# SCH_10_1HD_2022-05-30.net
KiCad netlist of a schematic drawn in EasyEDA
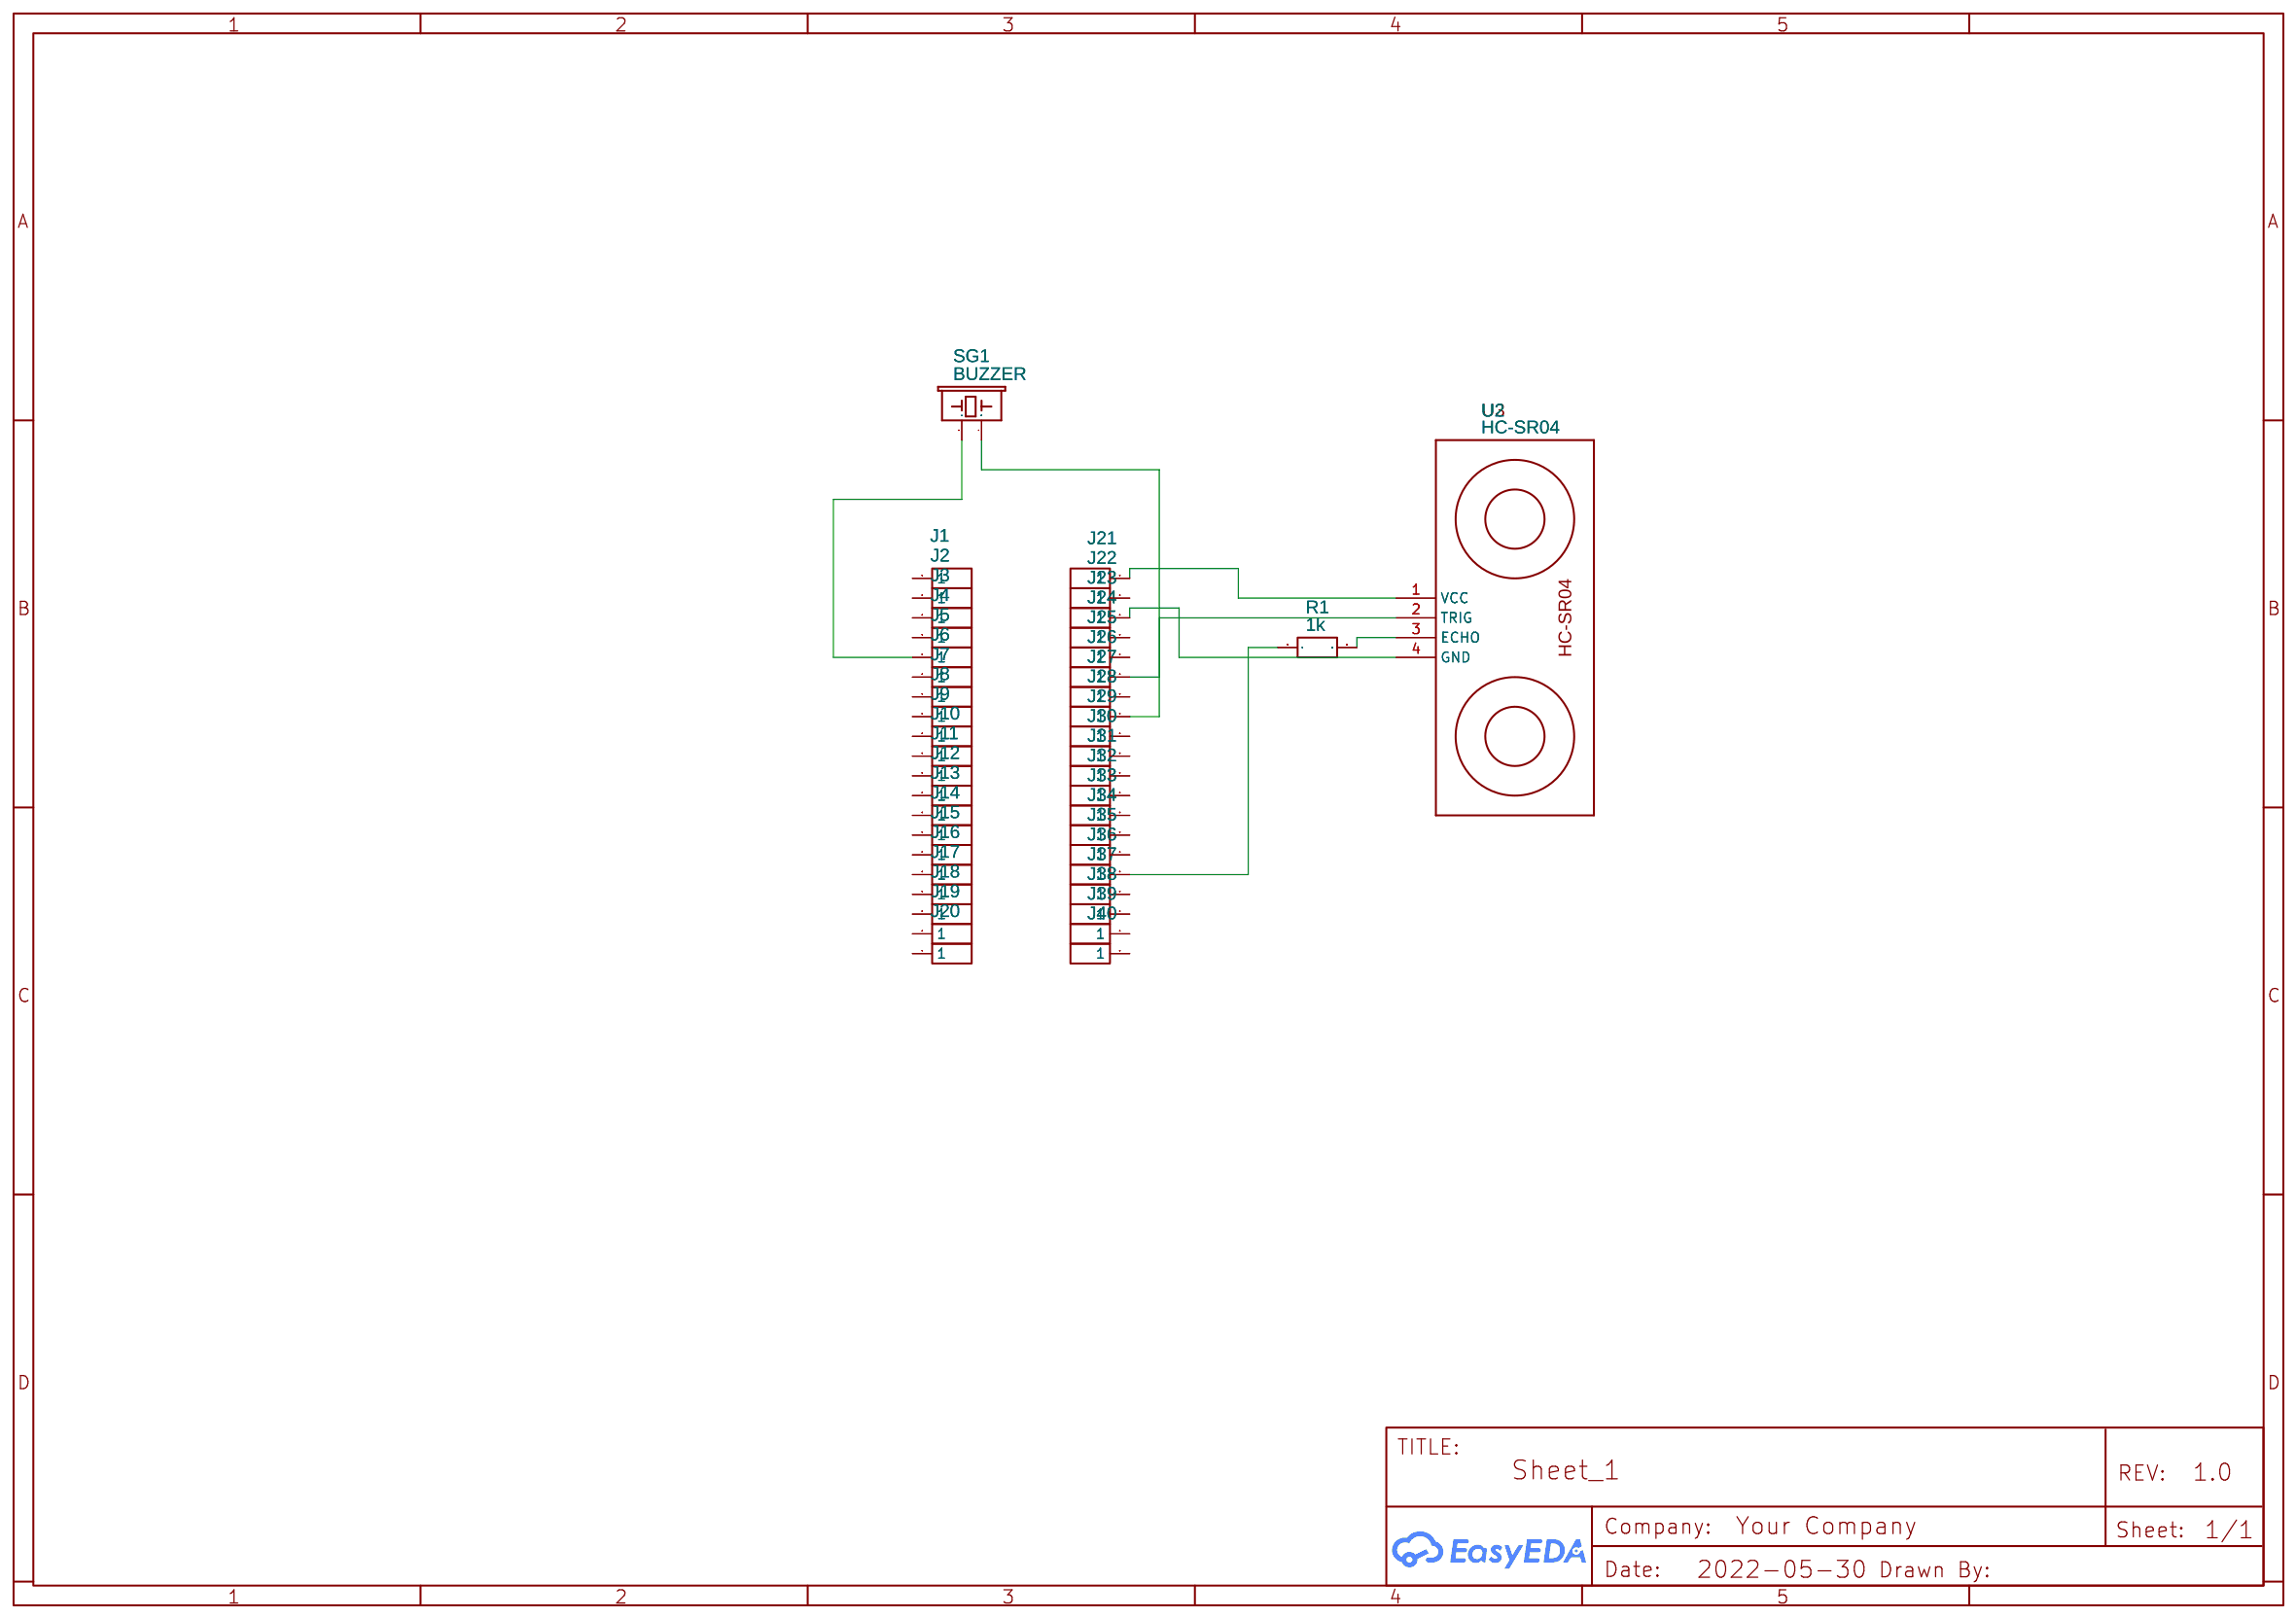
[diagram p0: schematic sheet]

(export (version "E")
  (design (tool "Eeschema 10.0.6"))
  (components
    (comp (ref "J1")
      (value "HDR-M-2.54_1x1")
      (fields (field (name "BOM_Supplier Part") "C81276"))
      (libsource (lib "") (part "HDR-M-2.54_1x1_1"))
    )
    (comp (ref "J2")
      (value "HDR-M-2.54_1x1")
      (fields (field (name "BOM_Supplier Part") "C81276"))
      (libsource (lib "") (part "HDR-M-2.54_1x1_1"))
    )
    (comp (ref "J3")
      (value "HDR-M-2.54_1x1")
      (fields (field (name "BOM_Supplier Part") "C81276"))
      (libsource (lib "") (part "HDR-M-2.54_1x1_1"))
    )
    (comp (ref "J4")
      (value "HDR-M-2.54_1x1")
      (fields (field (name "BOM_Supplier Part") "C81276"))
      (libsource (lib "") (part "HDR-M-2.54_1x1_1"))
    )
    (comp (ref "J5")
      (value "HDR-M-2.54_1x1")
      (fields (field (name "BOM_Supplier Part") "C81276"))
      (libsource (lib "") (part "HDR-M-2.54_1x1_1"))
    )
    (comp (ref "J6")
      (value "HDR-M-2.54_1x1")
      (fields (field (name "BOM_Supplier Part") "C81276"))
      (libsource (lib "") (part "HDR-M-2.54_1x1_1"))
    )
    (comp (ref "J7")
      (value "HDR-M-2.54_1x1")
      (fields (field (name "BOM_Supplier Part") "C81276"))
      (libsource (lib "") (part "HDR-M-2.54_1x1_1"))
    )
    (comp (ref "J8")
      (value "HDR-M-2.54_1x1")
      (fields (field (name "BOM_Supplier Part") "C81276"))
      (libsource (lib "") (part "HDR-M-2.54_1x1_1"))
    )
    (comp (ref "J9")
      (value "HDR-M-2.54_1x1")
      (fields (field (name "BOM_Supplier Part") "C81276"))
      (libsource (lib "") (part "HDR-M-2.54_1x1_1"))
    )
    (comp (ref "J10")
      (value "HDR-M-2.54_1x1")
      (fields (field (name "BOM_Supplier Part") "C81276"))
      (libsource (lib "") (part "HDR-M-2.54_1x1_1"))
    )
    (comp (ref "J11")
      (value "HDR-M-2.54_1x1")
      (fields (field (name "BOM_Supplier Part") "C81276"))
      (libsource (lib "") (part "HDR-M-2.54_1x1_1"))
    )
    (comp (ref "J12")
      (value "HDR-M-2.54_1x1")
      (fields (field (name "BOM_Supplier Part") "C81276"))
      (libsource (lib "") (part "HDR-M-2.54_1x1_1"))
    )
    (comp (ref "J13")
      (value "HDR-M-2.54_1x1")
      (fields (field (name "BOM_Supplier Part") "C81276"))
      (libsource (lib "") (part "HDR-M-2.54_1x1_1"))
    )
    (comp (ref "J14")
      (value "HDR-M-2.54_1x1")
      (fields (field (name "BOM_Supplier Part") "C81276"))
      (libsource (lib "") (part "HDR-M-2.54_1x1_1"))
    )
    (comp (ref "J15")
      (value "HDR-M-2.54_1x1")
      (fields (field (name "BOM_Supplier Part") "C81276"))
      (libsource (lib "") (part "HDR-M-2.54_1x1_1"))
    )
    (comp (ref "J16")
      (value "HDR-M-2.54_1x1")
      (fields (field (name "BOM_Supplier Part") "C81276"))
      (libsource (lib "") (part "HDR-M-2.54_1x1_1"))
    )
    (comp (ref "J17")
      (value "HDR-M-2.54_1x1")
      (fields (field (name "BOM_Supplier Part") "C81276"))
      (libsource (lib "") (part "HDR-M-2.54_1x1_1"))
    )
    (comp (ref "J18")
      (value "HDR-M-2.54_1x1")
      (fields (field (name "BOM_Supplier Part") "C81276"))
      (libsource (lib "") (part "HDR-M-2.54_1x1_1"))
    )
    (comp (ref "J19")
      (value "HDR-M-2.54_1x1")
      (fields (field (name "BOM_Supplier Part") "C81276"))
      (libsource (lib "") (part "HDR-M-2.54_1x1_1"))
    )
    (comp (ref "J20")
      (value "HDR-M-2.54_1x1")
      (fields (field (name "BOM_Supplier Part") "C81276"))
      (libsource (lib "") (part "HDR-M-2.54_1x1_1"))
    )
    (comp (ref "J21")
      (value "HDR-M-2.54_1x1")
      (fields (field (name "BOM_Supplier Part") "C81276"))
      (libsource (lib "") (part "HDR-M-2.54_1x1"))
    )
    (comp (ref "J22")
      (value "HDR-M-2.54_1x1")
      (fields (field (name "BOM_Supplier Part") "C81276"))
      (libsource (lib "") (part "HDR-M-2.54_1x1"))
    )
    (comp (ref "J23")
      (value "HDR-M-2.54_1x1")
      (fields (field (name "BOM_Supplier Part") "C81276"))
      (libsource (lib "") (part "HDR-M-2.54_1x1"))
    )
    (comp (ref "J24")
      (value "HDR-M-2.54_1x1")
      (fields (field (name "BOM_Supplier Part") "C81276"))
      (libsource (lib "") (part "HDR-M-2.54_1x1"))
    )
    (comp (ref "J25")
      (value "HDR-M-2.54_1x1")
      (fields (field (name "BOM_Supplier Part") "C81276"))
      (libsource (lib "") (part "HDR-M-2.54_1x1"))
    )
    (comp (ref "J26")
      (value "HDR-M-2.54_1x1")
      (fields (field (name "BOM_Supplier Part") "C81276"))
      (libsource (lib "") (part "HDR-M-2.54_1x1"))
    )
    (comp (ref "J27")
      (value "HDR-M-2.54_1x1")
      (fields (field (name "BOM_Supplier Part") "C81276"))
      (libsource (lib "") (part "HDR-M-2.54_1x1"))
    )
    (comp (ref "J28")
      (value "HDR-M-2.54_1x1")
      (fields (field (name "BOM_Supplier Part") "C81276"))
      (libsource (lib "") (part "HDR-M-2.54_1x1"))
    )
    (comp (ref "J29")
      (value "HDR-M-2.54_1x1")
      (fields (field (name "BOM_Supplier Part") "C81276"))
      (libsource (lib "") (part "HDR-M-2.54_1x1"))
    )
    (comp (ref "J30")
      (value "HDR-M-2.54_1x1")
      (fields (field (name "BOM_Supplier Part") "C81276"))
      (libsource (lib "") (part "HDR-M-2.54_1x1"))
    )
    (comp (ref "J31")
      (value "HDR-M-2.54_1x1")
      (fields (field (name "BOM_Supplier Part") "C81276"))
      (libsource (lib "") (part "HDR-M-2.54_1x1"))
    )
    (comp (ref "J32")
      (value "HDR-M-2.54_1x1")
      (fields (field (name "BOM_Supplier Part") "C81276"))
      (libsource (lib "") (part "HDR-M-2.54_1x1"))
    )
    (comp (ref "J33")
      (value "HDR-M-2.54_1x1")
      (fields (field (name "BOM_Supplier Part") "C81276"))
      (libsource (lib "") (part "HDR-M-2.54_1x1"))
    )
    (comp (ref "J34")
      (value "HDR-M-2.54_1x1")
      (fields (field (name "BOM_Supplier Part") "C81276"))
      (libsource (lib "") (part "HDR-M-2.54_1x1"))
    )
    (comp (ref "J35")
      (value "HDR-M-2.54_1x1")
      (fields (field (name "BOM_Supplier Part") "C81276"))
      (libsource (lib "") (part "HDR-M-2.54_1x1"))
    )
    (comp (ref "J36")
      (value "HDR-M-2.54_1x1")
      (fields (field (name "BOM_Supplier Part") "C81276"))
      (libsource (lib "") (part "HDR-M-2.54_1x1"))
    )
    (comp (ref "J37")
      (value "HDR-M-2.54_1x1")
      (fields (field (name "BOM_Supplier Part") "C81276"))
      (libsource (lib "") (part "HDR-M-2.54_1x1"))
    )
    (comp (ref "J38")
      (value "HDR-M-2.54_1x1")
      (fields (field (name "BOM_Supplier Part") "C81276"))
      (libsource (lib "") (part "HDR-M-2.54_1x1"))
    )
    (comp (ref "J39")
      (value "HDR-M-2.54_1x1")
      (fields (field (name "BOM_Supplier Part") "C81276"))
      (libsource (lib "") (part "HDR-M-2.54_1x1"))
    )
    (comp (ref "J40")
      (value "HDR-M-2.54_1x1")
      (fields (field (name "BOM_Supplier Part") "C81276"))
      (libsource (lib "") (part "HDR-M-2.54_1x1"))
    )
    (comp (ref "R1") (value "1k") (libsource (lib "") (part "R_0603_EU")))
    (comp (ref "SG1") (value "BUZZER") (libsource (lib "") (part "BUZZER")))
    (comp (ref "U2")
      (value "HC-SR04")
      (fields (field (name "BOM_Manufacturer Part") "ServoMotor"))
      (libsource (lib "") (part "HC-SR04"))
    )
  )
  (nets
    (net (code "1") (name "Net-(J36-Pad1)") (class "Default")
      (node (ref "J36") (pin "1") (pinfunction "1_1") (pintype "input"))
      (node (ref "R1") (pin "1") (pinfunction "1_1") (pintype "unspecified"))
    )
    (net (code "2") (name "Net-(SG1-1)") (class "Default")
      (node (ref "J5") (pin "1") (pinfunction "1_1") (pintype "input"))
      (node (ref "SG1") (pin "+") (pinfunction "1_+") (pintype "unspecified"))
    )
    (net (code "3") (name "Net-(SG1-2)") (class "Default")
      (node (ref "J28") (pin "1") (pinfunction "1_1") (pintype "input"))
      (node (ref "SG1") (pin "-") (pinfunction "2_-") (pintype "unspecified"))
    )
    (net (code "4") (name "Net-(U2-ECHO)") (class "Default")
      (node (ref "R1") (pin "2") (pinfunction "2_2") (pintype "unspecified"))
      (node (ref "U2") (pin "3") (pinfunction "ECHO_3") (pintype "output"))
    )
    (net (code "5") (name "Net-(U2-GND)") (class "Default")
      (node (ref "J23") (pin "1") (pinfunction "1_1") (pintype "input"))
      (node (ref "U2") (pin "4") (pinfunction "GND_4") (pintype "passive"))
    )
    (net (code "6") (name "Net-(U2-TRIG)") (class "Default")
      (node (ref "J26") (pin "1") (pinfunction "1_1") (pintype "input"))
      (node (ref "U2") (pin "2") (pinfunction "TRIG_2") (pintype "input"))
    )
    (net (code "7") (name "Net-(U2-VCC)") (class "Default")
      (node (ref "J21") (pin "1") (pinfunction "1_1") (pintype "input"))
      (node (ref "U2") (pin "1") (pinfunction "VCC_1") (pintype "passive"))
    )
    (net (code "8") (name "unconnected-(J1-Pad1)") (class "Default")
      (node (ref "J1") (pin "1") (pinfunction "1_1") (pintype "input"))
    )
    (net (code "9") (name "unconnected-(J2-Pad1)") (class "Default")
      (node (ref "J2") (pin "1") (pinfunction "1_1") (pintype "input"))
    )
    (net (code "10") (name "unconnected-(J3-Pad1)") (class "Default")
      (node (ref "J3") (pin "1") (pinfunction "1_1") (pintype "input"))
    )
    (net (code "11") (name "unconnected-(J4-Pad1)") (class "Default")
      (node (ref "J4") (pin "1") (pinfunction "1_1") (pintype "input"))
    )
    (net (code "12") (name "unconnected-(J6-Pad1)") (class "Default")
      (node (ref "J6") (pin "1") (pinfunction "1_1") (pintype "input"))
    )
    (net (code "13") (name "unconnected-(J7-Pad1)") (class "Default")
      (node (ref "J7") (pin "1") (pinfunction "1_1") (pintype "input"))
    )
    (net (code "14") (name "unconnected-(J8-Pad1)") (class "Default")
      (node (ref "J8") (pin "1") (pinfunction "1_1") (pintype "input"))
    )
    (net (code "15") (name "unconnected-(J9-Pad1)") (class "Default")
      (node (ref "J9") (pin "1") (pinfunction "1_1") (pintype "input"))
    )
    (net (code "16") (name "unconnected-(J10-Pad1)") (class "Default")
      (node (ref "J10") (pin "1") (pinfunction "1_1") (pintype "input"))
    )
    (net (code "17") (name "unconnected-(J11-Pad1)") (class "Default")
      (node (ref "J11") (pin "1") (pinfunction "1_1") (pintype "input"))
    )
    (net (code "18") (name "unconnected-(J12-Pad1)") (class "Default")
      (node (ref "J12") (pin "1") (pinfunction "1_1") (pintype "input"))
    )
    (net (code "19") (name "unconnected-(J13-Pad1)") (class "Default")
      (node (ref "J13") (pin "1") (pinfunction "1_1") (pintype "input"))
    )
    (net (code "20") (name "unconnected-(J14-Pad1)") (class "Default")
      (node (ref "J14") (pin "1") (pinfunction "1_1") (pintype "input"))
    )
    (net (code "21") (name "unconnected-(J15-Pad1)") (class "Default")
      (node (ref "J15") (pin "1") (pinfunction "1_1") (pintype "input"))
    )
    (net (code "22") (name "unconnected-(J16-Pad1)") (class "Default")
      (node (ref "J16") (pin "1") (pinfunction "1_1") (pintype "input"))
    )
    (net (code "23") (name "unconnected-(J17-Pad1)") (class "Default")
      (node (ref "J17") (pin "1") (pinfunction "1_1") (pintype "input"))
    )
    (net (code "24") (name "unconnected-(J18-Pad1)") (class "Default")
      (node (ref "J18") (pin "1") (pinfunction "1_1") (pintype "input"))
    )
    (net (code "25") (name "unconnected-(J19-Pad1)") (class "Default")
      (node (ref "J19") (pin "1") (pinfunction "1_1") (pintype "input"))
    )
    (net (code "26") (name "unconnected-(J20-Pad1)") (class "Default")
      (node (ref "J20") (pin "1") (pinfunction "1_1") (pintype "input"))
    )
    (net (code "27") (name "unconnected-(J22-Pad1)") (class "Default")
      (node (ref "J22") (pin "1") (pinfunction "1_1") (pintype "input"))
    )
    (net (code "28") (name "unconnected-(J24-Pad1)") (class "Default")
      (node (ref "J24") (pin "1") (pinfunction "1_1") (pintype "input"))
    )
    (net (code "29") (name "unconnected-(J25-Pad1)") (class "Default")
      (node (ref "J25") (pin "1") (pinfunction "1_1") (pintype "input"))
    )
    (net (code "30") (name "unconnected-(J27-Pad1)") (class "Default")
      (node (ref "J27") (pin "1") (pinfunction "1_1") (pintype "input"))
    )
    (net (code "31") (name "unconnected-(J29-Pad1)") (class "Default")
      (node (ref "J29") (pin "1") (pinfunction "1_1") (pintype "input"))
    )
    (net (code "32") (name "unconnected-(J30-Pad1)") (class "Default")
      (node (ref "J30") (pin "1") (pinfunction "1_1") (pintype "input"))
    )
    (net (code "33") (name "unconnected-(J31-Pad1)") (class "Default")
      (node (ref "J31") (pin "1") (pinfunction "1_1") (pintype "input"))
    )
    (net (code "34") (name "unconnected-(J32-Pad1)") (class "Default")
      (node (ref "J32") (pin "1") (pinfunction "1_1") (pintype "input"))
    )
    (net (code "35") (name "unconnected-(J33-Pad1)") (class "Default")
      (node (ref "J33") (pin "1") (pinfunction "1_1") (pintype "input"))
    )
    (net (code "36") (name "unconnected-(J34-Pad1)") (class "Default")
      (node (ref "J34") (pin "1") (pinfunction "1_1") (pintype "input"))
    )
    (net (code "37") (name "unconnected-(J35-Pad1)") (class "Default")
      (node (ref "J35") (pin "1") (pinfunction "1_1") (pintype "input"))
    )
    (net (code "38") (name "unconnected-(J37-Pad1)") (class "Default")
      (node (ref "J37") (pin "1") (pinfunction "1_1") (pintype "input"))
    )
    (net (code "39") (name "unconnected-(J38-Pad1)") (class "Default")
      (node (ref "J38") (pin "1") (pinfunction "1_1") (pintype "input"))
    )
    (net (code "40") (name "unconnected-(J39-Pad1)") (class "Default")
      (node (ref "J39") (pin "1") (pinfunction "1_1") (pintype "input"))
    )
    (net (code "41") (name "unconnected-(J40-Pad1)") (class "Default")
      (node (ref "J40") (pin "1") (pinfunction "1_1") (pintype "input"))
    )
  )
)
